# Raspberry_etherIO_v2.net
KiCad netlist of a schematic drawn in Altium Designer
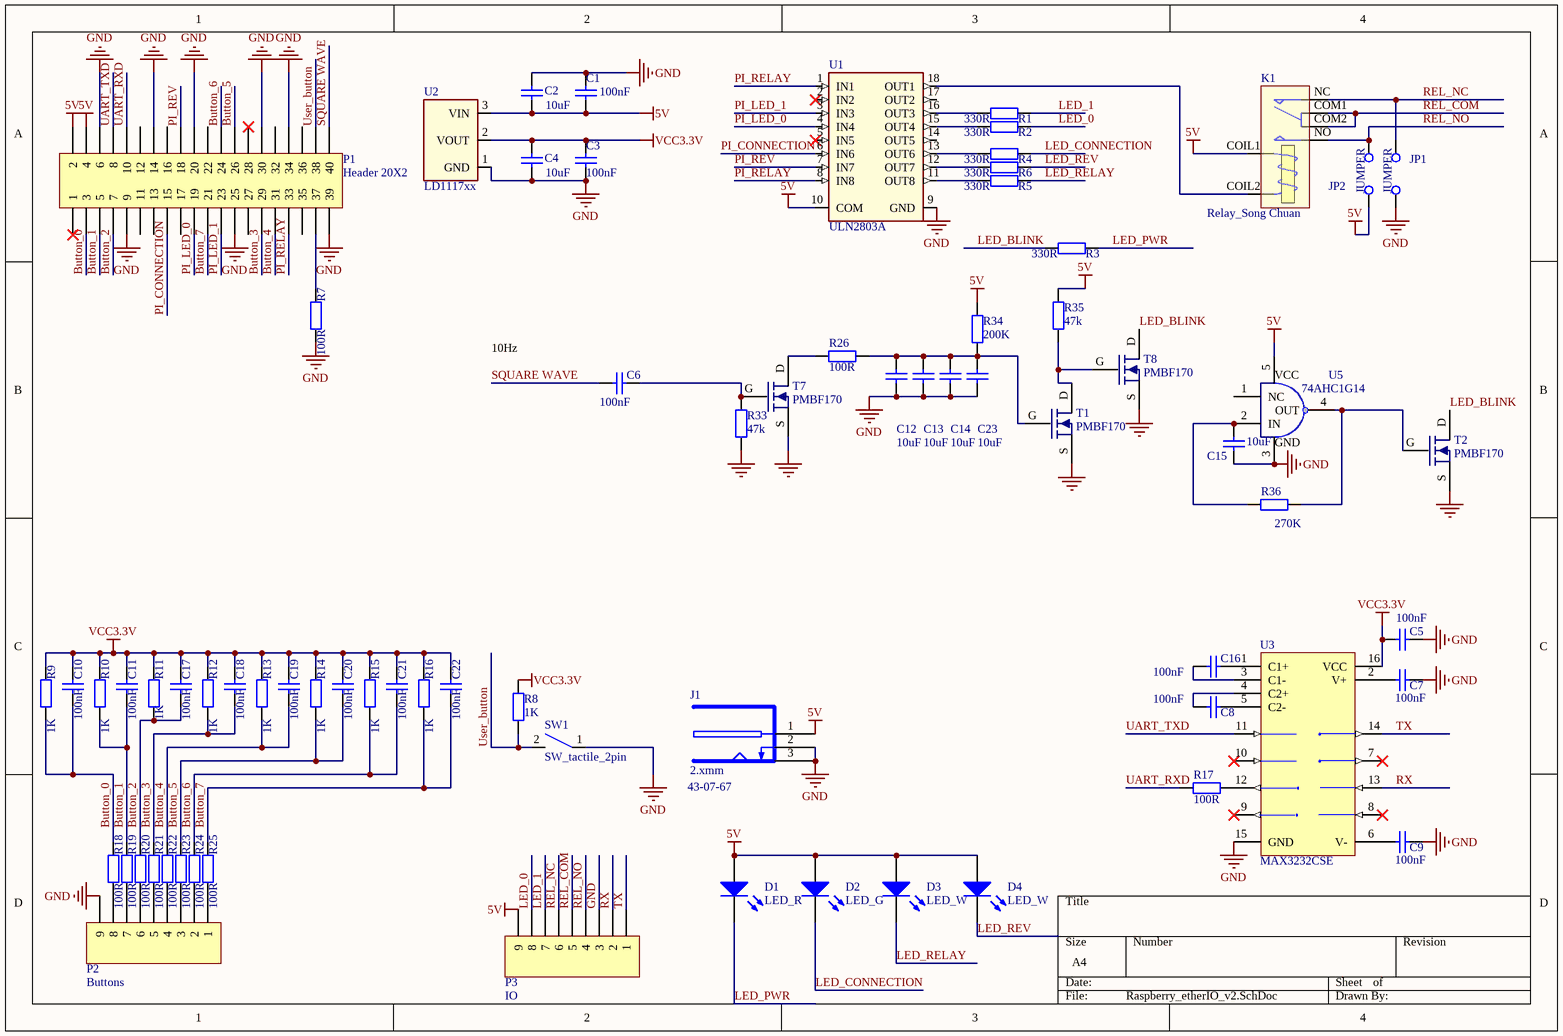
[diagram p0: Raspberry_etherIO_v2.SchDoc]

(export (version "E")
  (design (tool "Eeschema 10.0.6"))
  (components
    (comp (ref "C1")
      (value "100nF")
      (footprint "FP_0603_CAP_080")
      (description "Capacitor")
      (fields (field (name "PUBLISHER") "Altium Limited"))
      (libsource (lib "Miscellaneous Devices") (part "Cap"))
    )
    (comp (ref "C2")
      (value "10uF")
      (footprint "FP_1206_CAP_085")
      (description "Capacitor")
      (fields (field (name "PUBLISHER") "Altium Limited"))
      (libsource (lib "Miscellaneous Devices") (part "Cap"))
    )
    (comp (ref "C3")
      (value "100nF")
      (footprint "FP_0603_CAP_080")
      (description "Capacitor")
      (fields (field (name "PUBLISHER") "Altium Limited"))
      (libsource (lib "Miscellaneous Devices") (part "Cap"))
    )
    (comp (ref "C4")
      (value "10uF")
      (footprint "FP_1206_CAP_085")
      (description "Capacitor")
      (fields (field (name "PUBLISHER") "Altium Limited"))
      (libsource (lib "Miscellaneous Devices") (part "Cap"))
    )
    (comp (ref "C5")
      (value "100nF")
      (footprint "FP_0603_CAP_080")
      (description "Capacitor")
      (libsource (lib "Capacitor") (part "CAP"))
    )
    (comp (ref "C6")
      (value "100nF")
      (footprint "FP_0603_CAP_080")
      (description "Capacitor")
      (libsource (lib "Capacitor") (part "CAP"))
    )
    (comp (ref "C7")
      (value "100nF")
      (footprint "FP_0603_CAP_080")
      (description "Capacitor")
      (libsource (lib "Capacitor") (part "CAP"))
    )
    (comp (ref "C8")
      (value "100nF")
      (footprint "FP_0603_CAP_080")
      (description "Capacitor")
      (libsource (lib "Capacitor") (part "CAP"))
    )
    (comp (ref "C9")
      (value "100nF")
      (footprint "FP_0603_CAP_080")
      (description "Capacitor")
      (libsource (lib "Capacitor") (part "CAP"))
    )
    (comp (ref "C10")
      (value "100nF")
      (footprint "FP_0603_CAP_080")
      (description "Capacitor")
      (libsource (lib "Capacitor") (part "CAP"))
    )
    (comp (ref "C11")
      (value "100nF")
      (footprint "FP_0603_CAP_080")
      (description "Capacitor")
      (libsource (lib "Capacitor") (part "CAP"))
    )
    (comp (ref "C12")
      (value "10uF")
      (footprint "FP_1206_CAP_085")
      (description "Capacitor")
      (fields (field (name "PUBLISHER") "Altium Limited"))
      (libsource (lib "Miscellaneous Devices") (part "Cap"))
    )
    (comp (ref "C13")
      (value "10uF")
      (footprint "FP_1206_CAP_085")
      (description "Capacitor")
      (fields (field (name "PUBLISHER") "Altium Limited"))
      (libsource (lib "Miscellaneous Devices") (part "Cap"))
    )
    (comp (ref "C14")
      (value "10uF")
      (footprint "FP_1206_CAP_085")
      (description "Capacitor")
      (fields (field (name "PUBLISHER") "Altium Limited"))
      (libsource (lib "Miscellaneous Devices") (part "Cap"))
    )
    (comp (ref "C15")
      (value "10uF")
      (footprint "FP_0603_CAP_080")
      (description "Capacitor")
      (fields (field (name "PUBLISHER") "Altium Limited"))
      (libsource (lib "Miscellaneous Devices") (part "Cap"))
    )
    (comp (ref "C16")
      (value "100nF")
      (footprint "FP_0603_CAP_080")
      (description "Capacitor")
      (libsource (lib "Capacitor") (part "CAP"))
    )
    (comp (ref "C17")
      (value "100nF")
      (footprint "FP_0603_CAP_080")
      (description "Capacitor")
      (libsource (lib "Capacitor") (part "CAP"))
    )
    (comp (ref "C18")
      (value "100nF")
      (footprint "FP_0603_CAP_080")
      (description "Capacitor")
      (libsource (lib "Capacitor") (part "CAP"))
    )
    (comp (ref "C19")
      (value "100nF")
      (footprint "FP_0603_CAP_080")
      (description "Capacitor")
      (libsource (lib "Capacitor") (part "CAP"))
    )
    (comp (ref "C20")
      (value "100nF")
      (footprint "FP_0603_CAP_080")
      (description "Capacitor")
      (libsource (lib "Capacitor") (part "CAP"))
    )
    (comp (ref "C21")
      (value "100nF")
      (footprint "FP_0603_CAP_080")
      (description "Capacitor")
      (libsource (lib "Capacitor") (part "CAP"))
    )
    (comp (ref "C22")
      (value "100nF")
      (footprint "FP_0603_CAP_080")
      (description "Capacitor")
      (libsource (lib "Capacitor") (part "CAP"))
    )
    (comp (ref "C23")
      (value "10uF")
      (footprint "FP_1206_CAP_085")
      (description "Capacitor")
      (fields (field (name "PUBLISHER") "Altium Limited"))
      (libsource (lib "Miscellaneous Devices") (part "Cap"))
    )
    (comp (ref "D1")
      (value "LED_R")
      (footprint "1206 LED Reversed")
      (description "Typical LED")
      (libsource (lib "Led_optical") (part "LED"))
    )
    (comp (ref "D2")
      (value "LED_G")
      (footprint "1206 LED Reversed")
      (description "Typical LED")
      (libsource (lib "Led_optical") (part "LED"))
    )
    (comp (ref "D3")
      (value "LED_W")
      (footprint "1206 LED Reversed")
      (description "Typical LED")
      (libsource (lib "Led_optical") (part "LED"))
    )
    (comp (ref "D4")
      (value "LED_W")
      (footprint "1206 LED Reversed")
      (description "Typical LED")
      (libsource (lib "Led_optical") (part "LED"))
    )
    (comp (ref "J1")
      (value "2.xmm")
      (footprint "FP_DC_TAP_ANYA")
      (description "2.xmm DC HEBA25 TÁPFESZÜLTSÉG ALJZAT ZÁRT, NYÁKBA 90°")
      (fields (field (name "ORDER INFO") "43-07-67"))
      (libsource (lib "Connector") (part "DC_TAP_ANYA"))
    )
    (comp (ref "JP1")
      (value "JUMPER")
      (footprint "FP_CONN2_TUSKE_254MM")
      (description "Jumper Wire")
      (libsource (lib "Other") (part "JUMPER"))
    )
    (comp (ref "JP2")
      (value "JUMPER")
      (footprint "FP_CONN2_TUSKE_254MM")
      (description "Jumper Wire")
      (libsource (lib "Other") (part "JUMPER"))
    )
    (comp (ref "K1")
      (value "Relay_Song Chuan")
      (footprint "Relay_Song Chuan")
      (description "SPDT Relay")
      (fields (field (name "PUBLISHER") "Altium Limited"))
      (libsource (lib "Switch") (part "Relay_Song Chuan"))
    )
    (comp (ref "P1")
      (value "Header 20X2")
      (footprint "Header_2X20_pin_2.54")
      (description "Header, 20-Pin, Dual row")
      (fields (field (name "PUBLISHER") "Altium Limited"))
      (libsource (lib "Miscellaneous Connectors") (part "Header 20X2"))
    )
    (comp (ref "P2")
      (value "Buttons")
      (footprint "Euroblock 3.5pitch 9P")
      (description "Header, 9-Pin")
      (fields (field (name "PUBLISHER") "Altium Limited"))
      (libsource (lib "Miscellaneous Connectors") (part "Header 9"))
    )
    (comp (ref "P3")
      (value "IO")
      (footprint "Euroblock 3.5pitch 9P")
      (description "Header, 9-Pin")
      (fields (field (name "PUBLISHER") "Altium Limited"))
      (libsource (lib "Miscellaneous Connectors") (part "Header 9"))
    )
    (comp (ref "R1")
      (value "330R")
      (footprint "FP_0603_RES")
      (description "Resistor")
      (libsource (lib "") (part "RES_1"))
    )
    (comp (ref "R2")
      (value "330R")
      (footprint "FP_0603_RES")
      (description "Resistor")
      (libsource (lib "") (part "RES_1"))
    )
    (comp (ref "R3")
      (value "330R")
      (footprint "FP_0603_RES")
      (description "Resistor")
      (libsource (lib "") (part "RES_1"))
    )
    (comp (ref "R4")
      (value "330R")
      (footprint "FP_0603_RES")
      (description "Resistor")
      (libsource (lib "") (part "RES_1"))
    )
    (comp (ref "R5")
      (value "330R")
      (footprint "FP_0603_RES")
      (description "Resistor")
      (libsource (lib "") (part "RES_1"))
    )
    (comp (ref "R6")
      (value "330R")
      (footprint "FP_0603_RES")
      (description "Resistor")
      (libsource (lib "") (part "RES_1"))
    )
    (comp (ref "R7")
      (value "100R")
      (footprint "FP_0603_RES")
      (description "Resistor")
      (libsource (lib "Resistor") (part "RES"))
    )
    (comp (ref "R8")
      (value "1K")
      (footprint "FP_0603_RES")
      (description "Resistor")
      (libsource (lib "") (part "RES_2"))
    )
    (comp (ref "R9")
      (value "1K")
      (footprint "FP_0603_RES")
      (description "Resistor")
      (libsource (lib "Resistor") (part "RES"))
    )
    (comp (ref "R10")
      (value "1K")
      (footprint "FP_0603_RES")
      (description "Resistor")
      (libsource (lib "Resistor") (part "RES"))
    )
    (comp (ref "R11")
      (value "1K")
      (footprint "FP_0603_RES")
      (description "Resistor")
      (libsource (lib "Resistor") (part "RES"))
    )
    (comp (ref "R12")
      (value "1K")
      (footprint "FP_0603_RES")
      (description "Resistor")
      (libsource (lib "Resistor") (part "RES"))
    )
    (comp (ref "R13")
      (value "1K")
      (footprint "FP_0603_RES")
      (description "Resistor")
      (libsource (lib "Resistor") (part "RES"))
    )
    (comp (ref "R14")
      (value "1K")
      (footprint "FP_0603_RES")
      (description "Resistor")
      (libsource (lib "Resistor") (part "RES"))
    )
    (comp (ref "R15")
      (value "1K")
      (footprint "FP_0603_RES")
      (description "Resistor")
      (libsource (lib "Resistor") (part "RES"))
    )
    (comp (ref "R16")
      (value "1K")
      (footprint "FP_0603_RES")
      (description "Resistor")
      (libsource (lib "Resistor") (part "RES"))
    )
    (comp (ref "R17")
      (value "100R")
      (footprint "FP_0603_RES")
      (description "Resistor")
      (libsource (lib "") (part "RES_3"))
    )
    (comp (ref "R18")
      (value "100R")
      (footprint "FP_0603_RES")
      (description "Resistor")
      (libsource (lib "Resistor") (part "RES"))
    )
    (comp (ref "R19")
      (value "100R")
      (footprint "FP_0603_RES")
      (description "Resistor")
      (libsource (lib "Resistor") (part "RES"))
    )
    (comp (ref "R20")
      (value "100R")
      (footprint "FP_0603_RES")
      (description "Resistor")
      (libsource (lib "Resistor") (part "RES"))
    )
    (comp (ref "R21")
      (value "100R")
      (footprint "FP_0603_RES")
      (description "Resistor")
      (libsource (lib "Resistor") (part "RES"))
    )
    (comp (ref "R22")
      (value "100R")
      (footprint "FP_0603_RES")
      (description "Resistor")
      (libsource (lib "Resistor") (part "RES"))
    )
    (comp (ref "R23")
      (value "100R")
      (footprint "FP_0603_RES")
      (description "Resistor")
      (libsource (lib "Resistor") (part "RES"))
    )
    (comp (ref "R24")
      (value "100R")
      (footprint "FP_0603_RES")
      (description "Resistor")
      (libsource (lib "Resistor") (part "RES"))
    )
    (comp (ref "R25")
      (value "100R")
      (footprint "FP_0603_RES")
      (description "Resistor")
      (libsource (lib "Resistor") (part "RES"))
    )
    (comp (ref "R26")
      (value "100R")
      (footprint "FP_0603_RES")
      (description "Resistor")
      (libsource (lib "") (part "RES_3"))
    )
    (comp (ref "R33")
      (value "47k")
      (footprint "FP_0603_RES")
      (description "Resistor")
      (libsource (lib "Resistor") (part "RES"))
    )
    (comp (ref "R34")
      (value "200K")
      (footprint "FP_0603_RES")
      (description "Resistor")
      (libsource (lib "Resistor") (part "RES"))
    )
    (comp (ref "R35")
      (value "47k")
      (footprint "FP_0603_RES")
      (description "Resistor")
      (libsource (lib "Resistor") (part "RES"))
    )
    (comp (ref "R36")
      (value "270K")
      (footprint "FP_0603_RES")
      (description "Resistor")
      (fields (field (name "PUBLISHER") "Altium Limited"))
      (libsource (lib "Miscellaneous Devices") (part "Res3"))
    )
    (comp (ref "SW1")
      (value "SW_tactile_2pin")
      (footprint "SW_TACT_2PIN")
      (libsource (lib "Switch") (part "SW_tactile_2pin"))
    )
    (comp (ref "T1") (value "PMBF170") (footprint "FET_SOT23") (libsource (lib "FET") (part "NMOS")))
    (comp (ref "T2") (value "PMBF170") (footprint "FET_SOT23") (libsource (lib "FET") (part "NMOS")))
    (comp (ref "T7") (value "PMBF170") (footprint "FET_SOT23") (libsource (lib "FET") (part "NMOS")))
    (comp (ref "T8") (value "PMBF170") (footprint "FET_SOT23") (libsource (lib "FET") (part "NMOS")))
    (comp (ref "U1")
      (value "ULN2803A")
      (footprint "DIGITAL_SOIC18W")
      (libsource (lib "Digital") (part "ULN280x"))
    )
    (comp (ref "U2")
      (value "LD1117xx")
      (footprint "SUPPLY_SOT223")
      (description "LD1117xx 3,3V lin reg")
      (libsource (lib "Supply") (part "LD1117xx"))
    )
    (comp (ref "U3")
      (value "MAX3232CSE")
      (footprint "DIGITAL_SOIC16")
      (description "3.0V TO 5.5V, Low-Power, up to 1Mbps, True RS-232 Transceiver Using Four 0.1µF External Capacitor")
      (fields (field (name "PUBLISHER") "Altium Limited"))
      (libsource (lib "Maxim Communication Transceiver") (part "MAX3232CSE"))
    )
    (comp (ref "U5")
      (value "74AHC1G14")
      (footprint "GATE_SOT23-5")
      (description "SCHMITT-TRIGGER INVERTER")
      (libsource (lib "Logic_gate") (part "74AHC1G14"))
    )
  )
  (nets
    (net (code "1") (name "/Button_0") (class "Default")
      (node (ref "C10") (pin "1") (pinfunction "1_1") (pintype "passive"))
      (node (ref "P1") (pin "3") (pinfunction "3_3") (pintype "passive"))
      (node (ref "R18") (pin "2") (pinfunction "2_2") (pintype "passive"))
      (node (ref "R9") (pin "1") (pinfunction "1_1") (pintype "passive"))
    )
    (net (code "2") (name "/Button_1") (class "Default")
      (node (ref "C11") (pin "1") (pinfunction "1_1") (pintype "passive"))
      (node (ref "P1") (pin "5") (pinfunction "5_5") (pintype "passive"))
      (node (ref "R10") (pin "1") (pinfunction "1_1") (pintype "passive"))
      (node (ref "R19") (pin "2") (pinfunction "2_2") (pintype "passive"))
    )
    (net (code "3") (name "/Button_2") (class "Default")
      (node (ref "C17") (pin "1") (pinfunction "1_1") (pintype "passive"))
      (node (ref "P1") (pin "7") (pinfunction "7_7") (pintype "passive"))
      (node (ref "R11") (pin "1") (pinfunction "1_1") (pintype "passive"))
      (node (ref "R20") (pin "2") (pinfunction "2_2") (pintype "passive"))
    )
    (net (code "4") (name "/Button_3") (class "Default")
      (node (ref "C18") (pin "1") (pinfunction "1_1") (pintype "passive"))
      (node (ref "P1") (pin "29") (pinfunction "29_29") (pintype "passive"))
      (node (ref "R12") (pin "1") (pinfunction "1_1") (pintype "passive"))
      (node (ref "R21") (pin "2") (pinfunction "2_2") (pintype "passive"))
    )
    (net (code "5") (name "/Button_4") (class "Default")
      (node (ref "C19") (pin "1") (pinfunction "1_1") (pintype "passive"))
      (node (ref "P1") (pin "31") (pinfunction "31_31") (pintype "passive"))
      (node (ref "R13") (pin "1") (pinfunction "1_1") (pintype "passive"))
      (node (ref "R22") (pin "2") (pinfunction "2_2") (pintype "passive"))
    )
    (net (code "6") (name "/Button_5") (class "Default")
      (node (ref "C20") (pin "1") (pinfunction "1_1") (pintype "passive"))
      (node (ref "P1") (pin "26") (pinfunction "26_26") (pintype "passive"))
      (node (ref "R14") (pin "1") (pinfunction "1_1") (pintype "passive"))
      (node (ref "R23") (pin "2") (pinfunction "2_2") (pintype "passive"))
    )
    (net (code "7") (name "/Button_6") (class "Default")
      (node (ref "C21") (pin "1") (pinfunction "1_1") (pintype "passive"))
      (node (ref "P1") (pin "24") (pinfunction "24_24") (pintype "passive"))
      (node (ref "R15") (pin "1") (pinfunction "1_1") (pintype "passive"))
      (node (ref "R24") (pin "2") (pinfunction "2_2") (pintype "passive"))
    )
    (net (code "8") (name "/Button_7") (class "Default")
      (node (ref "C22") (pin "1") (pinfunction "1_1") (pintype "passive"))
      (node (ref "P1") (pin "21") (pinfunction "21_21") (pintype "passive"))
      (node (ref "R16") (pin "1") (pinfunction "1_1") (pintype "passive"))
      (node (ref "R25") (pin "2") (pinfunction "2_2") (pintype "passive"))
    )
    (net (code "9") (name "/LED_0") (class "Default")
      (node (ref "P3") (pin "8") (pinfunction "8_8") (pintype "passive"))
      (node (ref "R2") (pin "2") (pinfunction "2_2") (pintype "passive"))
    )
    (net (code "10") (name "/LED_1") (class "Default")
      (node (ref "P3") (pin "7") (pinfunction "7_7") (pintype "passive"))
      (node (ref "R1") (pin "2") (pinfunction "2_2") (pintype "passive"))
    )
    (net (code "11") (name "/LED_BLINK") (class "Default")
      (node (ref "R3") (pin "1") (pinfunction "1_1") (pintype "passive"))
      (node (ref "T2") (pin "D") (pinfunction "D_D") (pintype "passive"))
      (node (ref "T8") (pin "D") (pinfunction "D_D") (pintype "passive"))
    )
    (net (code "12") (name "/LED_CONNECTION") (class "Default")
      (node (ref "D2") (pin "2") (pinfunction "K_2") (pintype "passive"))
      (node (ref "R4") (pin "2") (pinfunction "2_2") (pintype "passive"))
    )
    (net (code "13") (name "/LED_PWR") (class "Default")
      (node (ref "D1") (pin "2") (pinfunction "K_2") (pintype "passive"))
      (node (ref "R3") (pin "2") (pinfunction "2_2") (pintype "passive"))
    )
    (net (code "14") (name "/LED_RELAY") (class "Default")
      (node (ref "D3") (pin "2") (pinfunction "K_2") (pintype "passive"))
      (node (ref "R5") (pin "2") (pinfunction "2_2") (pintype "passive"))
    )
    (net (code "15") (name "/LED_REV") (class "Default")
      (node (ref "D4") (pin "2") (pinfunction "K_2") (pintype "passive"))
      (node (ref "R6") (pin "2") (pinfunction "2_2") (pintype "passive"))
    )
    (net (code "16") (name "/PI_CONNECTION") (class "Default")
      (node (ref "P1") (pin "15") (pinfunction "15_15") (pintype "passive"))
      (node (ref "U1") (pin "6") (pinfunction "IN6_6") (pintype "input"))
    )
    (net (code "17") (name "/PI_LED_0") (class "Default")
      (node (ref "P1") (pin "19") (pinfunction "19_19") (pintype "passive"))
      (node (ref "U1") (pin "4") (pinfunction "IN4_4") (pintype "input"))
    )
    (net (code "18") (name "/PI_LED_1") (class "Default")
      (node (ref "P1") (pin "23") (pinfunction "23_23") (pintype "passive"))
      (node (ref "U1") (pin "3") (pinfunction "IN3_3") (pintype "input"))
    )
    (net (code "19") (name "/PI_RELAY") (class "Default")
      (node (ref "P1") (pin "33") (pinfunction "33_33") (pintype "passive"))
      (node (ref "U1") (pin "1") (pinfunction "IN1_1") (pintype "input"))
      (node (ref "U1") (pin "8") (pinfunction "IN8_8") (pintype "input"))
    )
    (net (code "20") (name "/PI_REV") (class "Default")
      (node (ref "P1") (pin "18") (pinfunction "18_18") (pintype "passive"))
      (node (ref "U1") (pin "7") (pinfunction "IN7_7") (pintype "input"))
    )
    (net (code "21") (name "/REL_COM") (class "Default")
      (node (ref "K1") (pin "COM1") (pinfunction "COM_COM1") (pintype "passive"))
      (node (ref "K1") (pin "COM2") (pinfunction "COM_COM2") (pintype "passive"))
      (node (ref "P3") (pin "5") (pinfunction "5_5") (pintype "passive"))
    )
    (net (code "22") (name "/REL_NC") (class "Default")
      (node (ref "JP1") (pin "2") (pinfunction "C2_2") (pintype "passive"))
      (node (ref "K1") (pin "NC") (pinfunction "NC_NC") (pintype "passive"))
      (node (ref "P3") (pin "6") (pinfunction "6_6") (pintype "passive"))
    )
    (net (code "23") (name "/REL_NO") (class "Default")
      (node (ref "JP2") (pin "2") (pinfunction "C2_2") (pintype "passive"))
      (node (ref "K1") (pin "NO") (pinfunction "NO_NO") (pintype "passive"))
      (node (ref "P3") (pin "4") (pinfunction "4_4") (pintype "passive"))
    )
    (net (code "24") (name "/RX") (class "Default")
      (node (ref "P3") (pin "2") (pinfunction "2_2") (pintype "passive"))
      (node (ref "U3") (pin "13") (pinfunction "R1IN_13") (pintype "input"))
    )
    (net (code "25") (name "/SQUARE WAVE") (class "Default")
      (node (ref "C6") (pin "1") (pinfunction "1_1") (pintype "passive"))
      (node (ref "P1") (pin "40") (pinfunction "40_40") (pintype "passive"))
    )
    (net (code "26") (name "/TX") (class "Default")
      (node (ref "P3") (pin "1") (pinfunction "1_1") (pintype "passive"))
      (node (ref "U3") (pin "14") (pinfunction "T1OUT_14") (pintype "output"))
    )
    (net (code "27") (name "/UART_RXD") (class "Default")
      (node (ref "P1") (pin "10") (pinfunction "10_10") (pintype "passive"))
      (node (ref "R17") (pin "2") (pinfunction "2_2") (pintype "passive"))
    )
    (net (code "28") (name "/UART_TXD") (class "Default")
      (node (ref "P1") (pin "8") (pinfunction "8_8") (pintype "passive"))
      (node (ref "U3") (pin "11") (pinfunction "T1IN_11") (pintype "input"))
    )
    (net (code "29") (name "/User_button") (class "Default")
      (node (ref "P1") (pin "38") (pinfunction "38_38") (pintype "passive"))
      (node (ref "R8") (pin "2") (pinfunction "2_2") (pintype "passive"))
      (node (ref "SW1") (pin "2") (pinfunction "2_2") (pintype "passive"))
    )
    (net (code "30") (name "5V") (class "Default")
      (node (ref "C1") (pin "2") (pinfunction "2_2") (pintype "passive"))
      (node (ref "C2") (pin "1") (pinfunction "1_1") (pintype "passive"))
      (node (ref "D1") (pin "1") (pinfunction "A_1") (pintype "passive"))
      (node (ref "D2") (pin "1") (pinfunction "A_1") (pintype "passive"))
      (node (ref "D3") (pin "1") (pinfunction "A_1") (pintype "passive"))
      (node (ref "D4") (pin "1") (pinfunction "A_1") (pintype "passive"))
      (node (ref "J1") (pin "1") (pinfunction "9V_1") (pintype "power_in"))
      (node (ref "JP2") (pin "1") (pinfunction "C1_1") (pintype "passive"))
      (node (ref "K1") (pin "COIL1") (pinfunction "COIL1_COIL1") (pintype "passive"))
      (node (ref "P1") (pin "2") (pinfunction "2_2") (pintype "passive"))
      (node (ref "P1") (pin "4") (pinfunction "4_4") (pintype "passive"))
      (node (ref "P3") (pin "9") (pinfunction "9_9") (pintype "passive"))
      (node (ref "R34") (pin "2") (pinfunction "2_2") (pintype "passive"))
      (node (ref "R35") (pin "2") (pinfunction "2_2") (pintype "passive"))
      (node (ref "U1") (pin "10") (pinfunction "COM_10") (pintype "passive"))
      (node (ref "U2") (pin "3") (pinfunction "VIN_3") (pintype "passive"))
      (node (ref "U5") (pin "5") (pinfunction "VCC_5") (pintype "passive"))
    )
    (net (code "31") (name "GND") (class "Default")
      (node (ref "C1") (pin "1") (pinfunction "1_1") (pintype "passive"))
      (node (ref "C12") (pin "1") (pinfunction "1_1") (pintype "passive"))
      (node (ref "C13") (pin "1") (pinfunction "1_1") (pintype "passive"))
      (node (ref "C14") (pin "1") (pinfunction "1_1") (pintype "passive"))
      (node (ref "C15") (pin "1") (pinfunction "1_1") (pintype "passive"))
      (node (ref "C2") (pin "2") (pinfunction "2_2") (pintype "passive"))
      (node (ref "C23") (pin "1") (pinfunction "1_1") (pintype "passive"))
      (node (ref "C3") (pin "2") (pinfunction "2_2") (pintype "passive"))
      (node (ref "C4") (pin "1") (pinfunction "1_1") (pintype "passive"))
      (node (ref "C5") (pin "2") (pinfunction "2_2") (pintype "passive"))
      (node (ref "C7") (pin "2") (pinfunction "2_2") (pintype "passive"))
      (node (ref "C9") (pin "2") (pinfunction "2_2") (pintype "passive"))
      (node (ref "J1") (pin "2") (pinfunction "GND_2") (pintype "power_in"))
      (node (ref "J1") (pin "3") (pinfunction "GND_3") (pintype "power_in"))
      (node (ref "JP1") (pin "1") (pinfunction "C1_1") (pintype "passive"))
      (node (ref "P1") (pin "14") (pinfunction "14_14") (pintype "passive"))
      (node (ref "P1") (pin "20") (pinfunction "20_20") (pintype "passive"))
      (node (ref "P1") (pin "25") (pinfunction "25_25") (pintype "passive"))
      (node (ref "P1") (pin "30") (pinfunction "30_30") (pintype "passive"))
      (node (ref "P1") (pin "34") (pinfunction "34_34") (pintype "passive"))
      (node (ref "P1") (pin "39") (pinfunction "39_39") (pintype "passive"))
      (node (ref "P1") (pin "6") (pinfunction "6_6") (pintype "passive"))
      (node (ref "P1") (pin "9") (pinfunction "9_9") (pintype "passive"))
      (node (ref "P2") (pin "9") (pinfunction "9_9") (pintype "passive"))
      (node (ref "P3") (pin "3") (pinfunction "3_3") (pintype "passive"))
      (node (ref "R33") (pin "1") (pinfunction "1_1") (pintype "passive"))
      (node (ref "R7") (pin "1") (pinfunction "1_1") (pintype "passive"))
      (node (ref "SW1") (pin "1") (pinfunction "1_1") (pintype "passive"))
      (node (ref "T1") (pin "S") (pinfunction "S_S") (pintype "passive"))
      (node (ref "T2") (pin "S") (pinfunction "S_S") (pintype "passive"))
      (node (ref "T7") (pin "S") (pinfunction "S_S") (pintype "passive"))
      (node (ref "T8") (pin "S") (pinfunction "S_S") (pintype "passive"))
      (node (ref "U1") (pin "9") (pinfunction "GND_9") (pintype "power_in"))
      (node (ref "U2") (pin "1") (pinfunction "GND_1") (pintype "passive"))
      (node (ref "U3") (pin "15") (pinfunction "GND_15") (pintype "power_in"))
      (node (ref "U5") (pin "3") (pinfunction "GND_3") (pintype "passive"))
    )
    (net (code "32") (name "Net-(C6-Pad2)") (class "Default")
      (node (ref "C6") (pin "2") (pinfunction "2_2") (pintype "passive"))
      (node (ref "R33") (pin "2") (pinfunction "2_2") (pintype "passive"))
      (node (ref "T7") (pin "G") (pinfunction "G_G") (pintype "passive"))
    )
    (net (code "33") (name "Net-(C12-Pad2)") (class "Default")
      (node (ref "C12") (pin "2") (pinfunction "2_2") (pintype "passive"))
      (node (ref "C13") (pin "2") (pinfunction "2_2") (pintype "passive"))
      (node (ref "C14") (pin "2") (pinfunction "2_2") (pintype "passive"))
      (node (ref "C23") (pin "2") (pinfunction "2_2") (pintype "passive"))
      (node (ref "R26") (pin "1") (pinfunction "1_1") (pintype "passive"))
      (node (ref "R34") (pin "1") (pinfunction "1_1") (pintype "passive"))
      (node (ref "T1") (pin "G") (pinfunction "G_G") (pintype "passive"))
    )
    (net (code "34") (name "Net-(P1-Pad37)") (class "Default")
      (node (ref "P1") (pin "37") (pinfunction "37_37") (pintype "passive"))
      (node (ref "R7") (pin "2") (pinfunction "2_2") (pintype "passive"))
    )
    (net (code "35") (name "Net-(P2-Pad1)") (class "Default")
      (node (ref "P2") (pin "1") (pinfunction "1_1") (pintype "passive"))
      (node (ref "R25") (pin "1") (pinfunction "1_1") (pintype "passive"))
    )
    (net (code "36") (name "Net-(P2-Pad2)") (class "Default")
      (node (ref "P2") (pin "2") (pinfunction "2_2") (pintype "passive"))
      (node (ref "R24") (pin "1") (pinfunction "1_1") (pintype "passive"))
    )
    (net (code "37") (name "Net-(P2-Pad3)") (class "Default")
      (node (ref "P2") (pin "3") (pinfunction "3_3") (pintype "passive"))
      (node (ref "R23") (pin "1") (pinfunction "1_1") (pintype "passive"))
    )
    (net (code "38") (name "Net-(P2-Pad4)") (class "Default")
      (node (ref "P2") (pin "4") (pinfunction "4_4") (pintype "passive"))
      (node (ref "R22") (pin "1") (pinfunction "1_1") (pintype "passive"))
    )
    (net (code "39") (name "Net-(P2-Pad5)") (class "Default")
      (node (ref "P2") (pin "5") (pinfunction "5_5") (pintype "passive"))
      (node (ref "R21") (pin "1") (pinfunction "1_1") (pintype "passive"))
    )
    (net (code "40") (name "Net-(P2-Pad6)") (class "Default")
      (node (ref "P2") (pin "6") (pinfunction "6_6") (pintype "passive"))
      (node (ref "R20") (pin "1") (pinfunction "1_1") (pintype "passive"))
    )
    (net (code "41") (name "Net-(P2-Pad7)") (class "Default")
      (node (ref "P2") (pin "7") (pinfunction "7_7") (pintype "passive"))
      (node (ref "R19") (pin "1") (pinfunction "1_1") (pintype "passive"))
    )
    (net (code "42") (name "Net-(P2-Pad8)") (class "Default")
      (node (ref "P2") (pin "8") (pinfunction "8_8") (pintype "passive"))
      (node (ref "R18") (pin "1") (pinfunction "1_1") (pintype "passive"))
    )
    (net (code "43") (name "Net-(R26-Pad2)") (class "Default")
      (node (ref "R26") (pin "2") (pinfunction "2_2") (pintype "passive"))
      (node (ref "T7") (pin "D") (pinfunction "D_D") (pintype "passive"))
    )
    (net (code "44") (name "Net-(R35-Pad1)") (class "Default")
      (node (ref "R35") (pin "1") (pinfunction "1_1") (pintype "passive"))
      (node (ref "T1") (pin "D") (pinfunction "D_D") (pintype "passive"))
      (node (ref "T8") (pin "G") (pinfunction "G_G") (pintype "passive"))
    )
    (net (code "45") (name "Net-(U1-OUT1)") (class "Default")
      (node (ref "K1") (pin "COIL2") (pinfunction "COIL2_COIL2") (pintype "passive"))
      (node (ref "U1") (pin "18") (pinfunction "OUT1_18") (pintype "output"))
    )
    (net (code "46") (name "Net-(U1-OUT3)") (class "Default")
      (node (ref "R1") (pin "1") (pinfunction "1_1") (pintype "passive"))
      (node (ref "U1") (pin "16") (pinfunction "OUT3_16") (pintype "output"))
    )
    (net (code "47") (name "Net-(U1-OUT4)") (class "Default")
      (node (ref "R2") (pin "1") (pinfunction "1_1") (pintype "passive"))
      (node (ref "U1") (pin "15") (pinfunction "OUT4_15") (pintype "output"))
    )
    (net (code "48") (name "Net-(U1-OUT6)") (class "Default")
      (node (ref "R4") (pin "1") (pinfunction "1_1") (pintype "passive"))
      (node (ref "U1") (pin "13") (pinfunction "OUT6_13") (pintype "output"))
    )
    (net (code "49") (name "Net-(U1-OUT7)") (class "Default")
      (node (ref "R6") (pin "1") (pinfunction "1_1") (pintype "passive"))
      (node (ref "U1") (pin "12") (pinfunction "OUT7_12") (pintype "output"))
    )
    (net (code "50") (name "Net-(U1-OUT8)") (class "Default")
      (node (ref "R5") (pin "1") (pinfunction "1_1") (pintype "passive"))
      (node (ref "U1") (pin "11") (pinfunction "OUT8_11") (pintype "output"))
    )
    (net (code "51") (name "Net-(U3-C1+)") (class "Default")
      (node (ref "C16") (pin "2") (pinfunction "2_2") (pintype "passive"))
      (node (ref "U3") (pin "1") (pinfunction "C1+_1") (pintype "passive"))
    )
    (net (code "52") (name "Net-(U3-C1-)") (class "Default")
      (node (ref "C16") (pin "1") (pinfunction "1_1") (pintype "passive"))
      (node (ref "U3") (pin "3") (pinfunction "C1-_3") (pintype "passive"))
    )
    (net (code "53") (name "Net-(U3-C2+)") (class "Default")
      (node (ref "C8") (pin "1") (pinfunction "1_1") (pintype "passive"))
      (node (ref "U3") (pin "4") (pinfunction "C2+_4") (pintype "passive"))
    )
    (net (code "54") (name "Net-(U3-C2-)") (class "Default")
      (node (ref "C8") (pin "2") (pinfunction "2_2") (pintype "passive"))
      (node (ref "U3") (pin "5") (pinfunction "C2-_5") (pintype "passive"))
    )
    (net (code "55") (name "Net-(U3-R1OUT)") (class "Default")
      (node (ref "R17") (pin "1") (pinfunction "1_1") (pintype "passive"))
      (node (ref "U3") (pin "12") (pinfunction "R1OUT_12") (pintype "output"))
    )
    (net (code "56") (name "Net-(U3-V+)") (class "Default")
      (node (ref "C7") (pin "1") (pinfunction "1_1") (pintype "passive"))
      (node (ref "U3") (pin "2") (pinfunction "V+_2") (pintype "power_in"))
    )
    (net (code "57") (name "Net-(U3-V-)") (class "Default")
      (node (ref "C9") (pin "1") (pinfunction "1_1") (pintype "passive"))
      (node (ref "U3") (pin "6") (pinfunction "V-_6") (pintype "power_in"))
    )
    (net (code "58") (name "Net-(U5-IN)") (class "Default")
      (node (ref "C15") (pin "2") (pinfunction "2_2") (pintype "passive"))
      (node (ref "R36") (pin "2") (pinfunction "2_2") (pintype "passive"))
      (node (ref "U5") (pin "2") (pinfunction "IN_2") (pintype "passive"))
    )
    (net (code "59") (name "Net-(U5-OUT)") (class "Default")
      (node (ref "R36") (pin "1") (pinfunction "1_1") (pintype "passive"))
      (node (ref "T2") (pin "G") (pinfunction "G_G") (pintype "passive"))
      (node (ref "U5") (pin "4") (pinfunction "OUT_4") (pintype "passive"))
    )
    (net (code "60") (name "VCC3.3V") (class "Default")
      (node (ref "C10") (pin "2") (pinfunction "2_2") (pintype "passive"))
      (node (ref "C11") (pin "2") (pinfunction "2_2") (pintype "passive"))
      (node (ref "C17") (pin "2") (pinfunction "2_2") (pintype "passive"))
      (node (ref "C18") (pin "2") (pinfunction "2_2") (pintype "passive"))
      (node (ref "C19") (pin "2") (pinfunction "2_2") (pintype "passive"))
      (node (ref "C20") (pin "2") (pinfunction "2_2") (pintype "passive"))
      (node (ref "C21") (pin "2") (pinfunction "2_2") (pintype "passive"))
      (node (ref "C22") (pin "2") (pinfunction "2_2") (pintype "passive"))
      (node (ref "C3") (pin "1") (pinfunction "1_1") (pintype "passive"))
      (node (ref "C4") (pin "2") (pinfunction "2_2") (pintype "passive"))
      (node (ref "C5") (pin "1") (pinfunction "1_1") (pintype "passive"))
      (node (ref "R10") (pin "2") (pinfunction "2_2") (pintype "passive"))
      (node (ref "R11") (pin "2") (pinfunction "2_2") (pintype "passive"))
      (node (ref "R12") (pin "2") (pinfunction "2_2") (pintype "passive"))
      (node (ref "R13") (pin "2") (pinfunction "2_2") (pintype "passive"))
      (node (ref "R14") (pin "2") (pinfunction "2_2") (pintype "passive"))
      (node (ref "R15") (pin "2") (pinfunction "2_2") (pintype "passive"))
      (node (ref "R16") (pin "2") (pinfunction "2_2") (pintype "passive"))
      (node (ref "R8") (pin "1") (pinfunction "1_1") (pintype "passive"))
      (node (ref "R9") (pin "2") (pinfunction "2_2") (pintype "passive"))
      (node (ref "U2") (pin "2") (pinfunction "VOUT_2") (pintype "passive"))
      (node (ref "U3") (pin "16") (pinfunction "VCC_16") (pintype "power_in"))
    )
    (net (code "61") (name "unconnected-(P1-Pad1)") (class "Default")
      (node (ref "P1") (pin "1") (pinfunction "1_1") (pintype "passive+no_connect"))
    )
    (net (code "62") (name "unconnected-(P1-Pad11)") (class "Default")
      (node (ref "P1") (pin "11") (pinfunction "11_11") (pintype "passive"))
    )
    (net (code "63") (name "unconnected-(P1-Pad12)") (class "Default")
      (node (ref "P1") (pin "12") (pinfunction "12_12") (pintype "passive"))
    )
    (net (code "64") (name "unconnected-(P1-Pad13)") (class "Default")
      (node (ref "P1") (pin "13") (pinfunction "13_13") (pintype "passive"))
    )
    (net (code "65") (name "unconnected-(P1-Pad16)") (class "Default")
      (node (ref "P1") (pin "16") (pinfunction "16_16") (pintype "passive"))
    )
    (net (code "66") (name "unconnected-(P1-Pad17)") (class "Default")
      (node (ref "P1") (pin "17") (pinfunction "17_17") (pintype "passive"))
    )
    (net (code "67") (name "unconnected-(P1-Pad22)") (class "Default")
      (node (ref "P1") (pin "22") (pinfunction "22_22") (pintype "passive"))
    )
    (net (code "68") (name "unconnected-(P1-Pad27)") (class "Default")
      (node (ref "P1") (pin "27") (pinfunction "27_27") (pintype "passive"))
    )
    (net (code "69") (name "unconnected-(P1-Pad28)") (class "Default")
      (node (ref "P1") (pin "28") (pinfunction "28_28") (pintype "passive+no_connect"))
    )
    (net (code "70") (name "unconnected-(P1-Pad32)") (class "Default")
      (node (ref "P1") (pin "32") (pinfunction "32_32") (pintype "passive"))
    )
    (net (code "71") (name "unconnected-(P1-Pad35)") (class "Default")
      (node (ref "P1") (pin "35") (pinfunction "35_35") (pintype "passive"))
    )
    (net (code "72") (name "unconnected-(P1-Pad36)") (class "Default")
      (node (ref "P1") (pin "36") (pinfunction "36_36") (pintype "passive"))
    )
    (net (code "73") (name "unconnected-(U1-IN2-Pad2)") (class "Default")
      (node (ref "U1") (pin "2") (pinfunction "IN2_2") (pintype "input+no_connect"))
    )
    (net (code "74") (name "unconnected-(U1-IN5-Pad5)") (class "Default")
      (node (ref "U1") (pin "5") (pinfunction "IN5_5") (pintype "input+no_connect"))
    )
    (net (code "75") (name "unconnected-(U1-OUT2-Pad17)") (class "Default")
      (node (ref "U1") (pin "17") (pinfunction "OUT2_17") (pintype "output"))
    )
    (net (code "76") (name "unconnected-(U1-OUT5-Pad14)") (class "Default")
      (node (ref "U1") (pin "14") (pinfunction "OUT5_14") (pintype "output"))
    )
    (net (code "77") (name "unconnected-(U3-R2IN-Pad8)") (class "Default")
      (node (ref "U3") (pin "8") (pinfunction "R2IN_8") (pintype "input+no_connect"))
    )
    (net (code "78") (name "unconnected-(U3-R2OUT-Pad9)") (class "Default")
      (node (ref "U3") (pin "9") (pinfunction "R2OUT_9") (pintype "output+no_connect"))
    )
    (net (code "79") (name "unconnected-(U3-T2IN-Pad10)") (class "Default")
      (node (ref "U3") (pin "10") (pinfunction "T2IN_10") (pintype "input+no_connect"))
    )
    (net (code "80") (name "unconnected-(U3-T2OUT-Pad7)") (class "Default")
      (node (ref "U3") (pin "7") (pinfunction "T2OUT_7") (pintype "output+no_connect"))
    )
    (net (code "81") (name "unconnected-(U5-NC-Pad1)") (class "Default")
      (node (ref "U5") (pin "1") (pinfunction "NC_1") (pintype "passive"))
    )
  )
)
